# bufferedBackplane.net
KiCad netlist of a schematic drawn in EAGLE
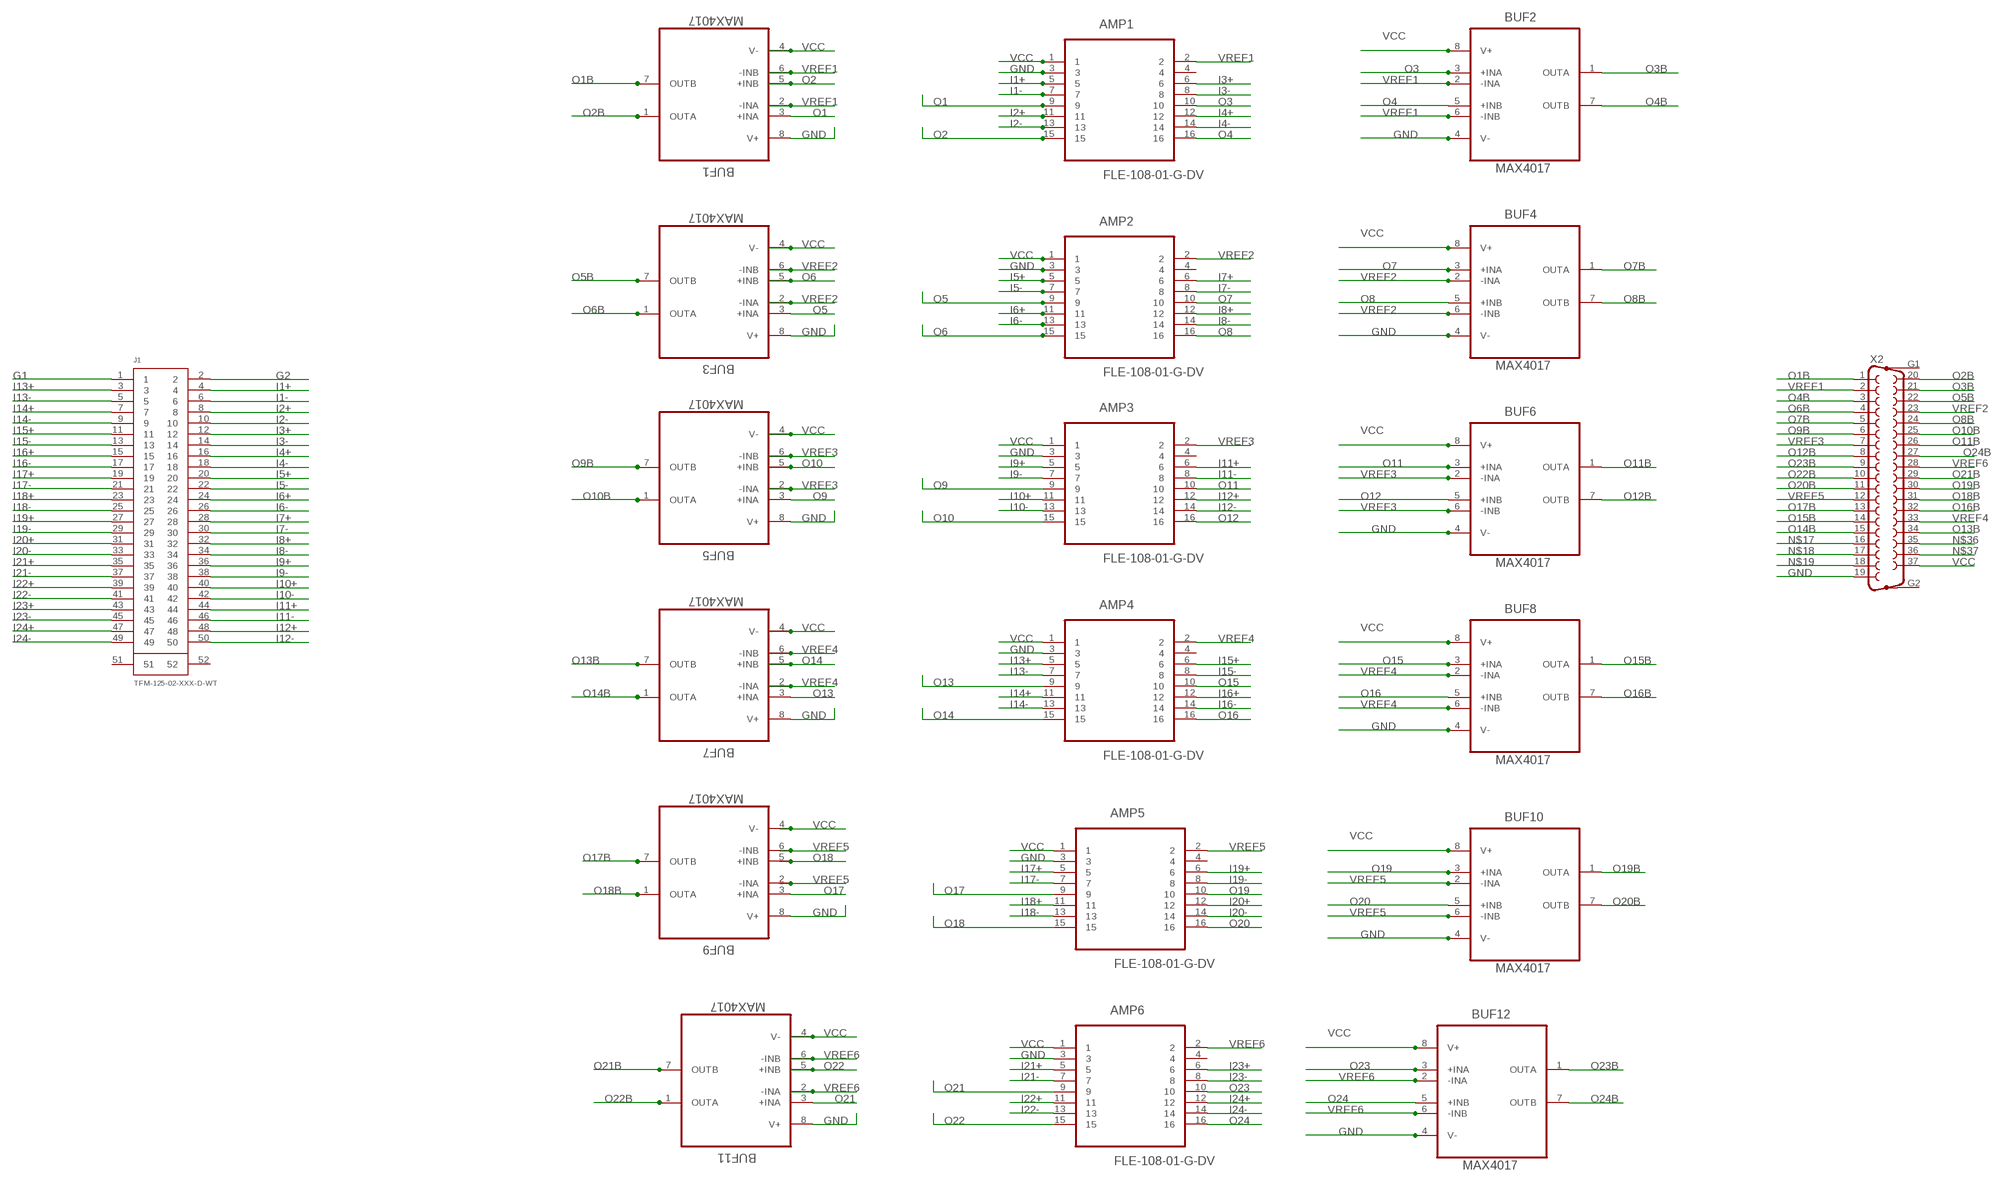
[diagram p0: schematic, sheet 1]

(export (version "E")
  (design (tool "Eeschema 10.0.6"))
  (components
    (comp (ref "AMP1")
      (value "FLE-108-01-G-DV")
      (footprint "eagle-import:SAMTEC_FLE-108-01-G-DV")
      (libsource (lib "eagle-import") (part "FLE-108-01-G-DV"))
    )
    (comp (ref "AMP2")
      (value "FLE-108-01-G-DV")
      (footprint "eagle-import:SAMTEC_FLE-108-01-G-DV")
      (libsource (lib "eagle-import") (part "FLE-108-01-G-DV"))
    )
    (comp (ref "AMP3")
      (value "FLE-108-01-G-DV")
      (footprint "eagle-import:SAMTEC_FLE-108-01-G-DV")
      (libsource (lib "eagle-import") (part "FLE-108-01-G-DV"))
    )
    (comp (ref "AMP4")
      (value "FLE-108-01-G-DV")
      (footprint "eagle-import:SAMTEC_FLE-108-01-G-DV")
      (libsource (lib "eagle-import") (part "FLE-108-01-G-DV"))
    )
    (comp (ref "AMP5")
      (value "FLE-108-01-G-DV")
      (footprint "eagle-import:SAMTEC_FLE-108-01-G-DV")
      (libsource (lib "eagle-import") (part "FLE-108-01-G-DV"))
    )
    (comp (ref "AMP6")
      (value "FLE-108-01-G-DV")
      (footprint "eagle-import:SAMTEC_FLE-108-01-G-DV")
      (libsource (lib "eagle-import") (part "FLE-108-01-G-DV"))
    )
    (comp (ref "BUF1")
      (value "MAX4017")
      (footprint "eagle-import:MAX4017")
      (libsource (lib "eagle-import") (part "MAX4017"))
    )
    (comp (ref "BUF2")
      (value "MAX4017")
      (footprint "eagle-import:MAX4017")
      (libsource (lib "eagle-import") (part "MAX4017"))
    )
    (comp (ref "BUF3")
      (value "MAX4017")
      (footprint "eagle-import:MAX4017")
      (libsource (lib "eagle-import") (part "MAX4017"))
    )
    (comp (ref "BUF4")
      (value "MAX4017")
      (footprint "eagle-import:MAX4017")
      (libsource (lib "eagle-import") (part "MAX4017"))
    )
    (comp (ref "BUF5")
      (value "MAX4017")
      (footprint "eagle-import:MAX4017")
      (libsource (lib "eagle-import") (part "MAX4017"))
    )
    (comp (ref "BUF6")
      (value "MAX4017")
      (footprint "eagle-import:MAX4017")
      (libsource (lib "eagle-import") (part "MAX4017"))
    )
    (comp (ref "BUF7")
      (value "MAX4017")
      (footprint "eagle-import:MAX4017")
      (libsource (lib "eagle-import") (part "MAX4017"))
    )
    (comp (ref "BUF8")
      (value "MAX4017")
      (footprint "eagle-import:MAX4017")
      (libsource (lib "eagle-import") (part "MAX4017"))
    )
    (comp (ref "BUF9")
      (value "MAX4017")
      (footprint "eagle-import:MAX4017")
      (libsource (lib "eagle-import") (part "MAX4017"))
    )
    (comp (ref "BUF10")
      (value "MAX4017")
      (footprint "eagle-import:MAX4017")
      (libsource (lib "eagle-import") (part "MAX4017"))
    )
    (comp (ref "BUF11")
      (value "MAX4017")
      (footprint "eagle-import:MAX4017")
      (libsource (lib "eagle-import") (part "MAX4017"))
    )
    (comp (ref "BUF12")
      (value "MAX4017")
      (footprint "eagle-import:MAX4017")
      (libsource (lib "eagle-import") (part "MAX4017"))
    )
    (comp (ref "J1")
      (value "TFM-125-02-XXX-D-WT")
      (footprint "eagle-import:TFM-125-02-XXX-D-WT")
      (libsource (lib "eagle-import") (part "TFM-125-02-XXX-D-WT"))
    )
    (comp (ref "X2")
      (value "F37HP")
      (footprint "eagle-import:F37HP")
      (libsource (lib "eagle-import") (part "F37HP"))
    )
  )
  (nets
    (net (code "1") (name "/G1") (class "Default")
      (node (ref "J1") (pin "1") (pinfunction "1_1") (pintype "bidirectional"))
    )
    (net (code "2") (name "/G2") (class "Default")
      (node (ref "J1") (pin "2") (pinfunction "2_2") (pintype "bidirectional"))
    )
    (net (code "3") (name "/GND") (class "Default")
      (node (ref "AMP1") (pin "3") (pinfunction "3_3") (pintype "passive"))
      (node (ref "AMP2") (pin "3") (pinfunction "3_3") (pintype "passive"))
      (node (ref "AMP3") (pin "3") (pinfunction "3_3") (pintype "passive"))
      (node (ref "AMP4") (pin "3") (pinfunction "3_3") (pintype "passive"))
      (node (ref "AMP5") (pin "3") (pinfunction "3_3") (pintype "passive"))
      (node (ref "AMP6") (pin "3") (pinfunction "3_3") (pintype "passive"))
      (node (ref "BUF1") (pin "8") (pinfunction "V+_8") (pintype "power_in"))
      (node (ref "BUF10") (pin "4") (pinfunction "V-_4") (pintype "power_in"))
      (node (ref "BUF11") (pin "8") (pinfunction "V+_8") (pintype "power_in"))
      (node (ref "BUF12") (pin "4") (pinfunction "V-_4") (pintype "power_in"))
      (node (ref "BUF2") (pin "4") (pinfunction "V-_4") (pintype "power_in"))
      (node (ref "BUF3") (pin "8") (pinfunction "V+_8") (pintype "power_in"))
      (node (ref "BUF4") (pin "4") (pinfunction "V-_4") (pintype "power_in"))
      (node (ref "BUF5") (pin "8") (pinfunction "V+_8") (pintype "power_in"))
      (node (ref "BUF6") (pin "4") (pinfunction "V-_4") (pintype "power_in"))
      (node (ref "BUF7") (pin "8") (pinfunction "V+_8") (pintype "power_in"))
      (node (ref "BUF8") (pin "4") (pinfunction "V-_4") (pintype "power_in"))
      (node (ref "BUF9") (pin "8") (pinfunction "V+_8") (pintype "power_in"))
      (node (ref "X2") (pin "19") (pinfunction "19_19") (pintype "passive"))
    )
    (net (code "4") (name "/I1+") (class "Default")
      (node (ref "AMP1") (pin "5") (pinfunction "5_5") (pintype "passive"))
      (node (ref "J1") (pin "4") (pinfunction "4_4") (pintype "bidirectional"))
    )
    (net (code "5") (name "/I1-") (class "Default")
      (node (ref "AMP1") (pin "7") (pinfunction "7_7") (pintype "passive"))
      (node (ref "J1") (pin "6") (pinfunction "6_6") (pintype "bidirectional"))
    )
    (net (code "6") (name "/I2+") (class "Default")
      (node (ref "AMP1") (pin "11") (pinfunction "11_11") (pintype "passive"))
      (node (ref "J1") (pin "8") (pinfunction "8_8") (pintype "bidirectional"))
    )
    (net (code "7") (name "/I2-") (class "Default")
      (node (ref "AMP1") (pin "13") (pinfunction "13_13") (pintype "passive"))
      (node (ref "J1") (pin "10") (pinfunction "10_10") (pintype "bidirectional"))
    )
    (net (code "8") (name "/I3+") (class "Default")
      (node (ref "AMP1") (pin "6") (pinfunction "6_6") (pintype "passive"))
      (node (ref "J1") (pin "12") (pinfunction "12_12") (pintype "bidirectional"))
    )
    (net (code "9") (name "/I3-") (class "Default")
      (node (ref "AMP1") (pin "8") (pinfunction "8_8") (pintype "passive"))
      (node (ref "J1") (pin "14") (pinfunction "14_14") (pintype "bidirectional"))
    )
    (net (code "10") (name "/I4+") (class "Default")
      (node (ref "AMP1") (pin "12") (pinfunction "12_12") (pintype "passive"))
      (node (ref "J1") (pin "16") (pinfunction "16_16") (pintype "bidirectional"))
    )
    (net (code "11") (name "/I4-") (class "Default")
      (node (ref "AMP1") (pin "14") (pinfunction "14_14") (pintype "passive"))
      (node (ref "J1") (pin "18") (pinfunction "18_18") (pintype "bidirectional"))
    )
    (net (code "12") (name "/I5+") (class "Default")
      (node (ref "AMP2") (pin "5") (pinfunction "5_5") (pintype "passive"))
      (node (ref "J1") (pin "20") (pinfunction "20_20") (pintype "bidirectional"))
    )
    (net (code "13") (name "/I5-") (class "Default")
      (node (ref "AMP2") (pin "7") (pinfunction "7_7") (pintype "passive"))
      (node (ref "J1") (pin "22") (pinfunction "22_22") (pintype "bidirectional"))
    )
    (net (code "14") (name "/I6+") (class "Default")
      (node (ref "AMP2") (pin "11") (pinfunction "11_11") (pintype "passive"))
      (node (ref "J1") (pin "24") (pinfunction "24_24") (pintype "bidirectional"))
    )
    (net (code "15") (name "/I6-") (class "Default")
      (node (ref "AMP2") (pin "13") (pinfunction "13_13") (pintype "passive"))
      (node (ref "J1") (pin "26") (pinfunction "26_26") (pintype "bidirectional"))
    )
    (net (code "16") (name "/I7+") (class "Default")
      (node (ref "AMP2") (pin "6") (pinfunction "6_6") (pintype "passive"))
      (node (ref "J1") (pin "28") (pinfunction "28_28") (pintype "bidirectional"))
    )
    (net (code "17") (name "/I7-") (class "Default")
      (node (ref "AMP2") (pin "8") (pinfunction "8_8") (pintype "passive"))
      (node (ref "J1") (pin "30") (pinfunction "30_30") (pintype "bidirectional"))
    )
    (net (code "18") (name "/I8+") (class "Default")
      (node (ref "AMP2") (pin "12") (pinfunction "12_12") (pintype "passive"))
      (node (ref "J1") (pin "32") (pinfunction "32_32") (pintype "bidirectional"))
    )
    (net (code "19") (name "/I8-") (class "Default")
      (node (ref "AMP2") (pin "14") (pinfunction "14_14") (pintype "passive"))
      (node (ref "J1") (pin "34") (pinfunction "34_34") (pintype "bidirectional"))
    )
    (net (code "20") (name "/I9+") (class "Default")
      (node (ref "AMP3") (pin "5") (pinfunction "5_5") (pintype "passive"))
      (node (ref "J1") (pin "36") (pinfunction "36_36") (pintype "bidirectional"))
    )
    (net (code "21") (name "/I9-") (class "Default")
      (node (ref "AMP3") (pin "7") (pinfunction "7_7") (pintype "passive"))
      (node (ref "J1") (pin "38") (pinfunction "38_38") (pintype "bidirectional"))
    )
    (net (code "22") (name "/I10+") (class "Default")
      (node (ref "AMP3") (pin "11") (pinfunction "11_11") (pintype "passive"))
      (node (ref "J1") (pin "40") (pinfunction "40_40") (pintype "bidirectional"))
    )
    (net (code "23") (name "/I10-") (class "Default")
      (node (ref "AMP3") (pin "13") (pinfunction "13_13") (pintype "passive"))
      (node (ref "J1") (pin "42") (pinfunction "42_42") (pintype "bidirectional"))
    )
    (net (code "24") (name "/I11+") (class "Default")
      (node (ref "AMP3") (pin "6") (pinfunction "6_6") (pintype "passive"))
      (node (ref "J1") (pin "44") (pinfunction "44_44") (pintype "bidirectional"))
    )
    (net (code "25") (name "/I11-") (class "Default")
      (node (ref "AMP3") (pin "8") (pinfunction "8_8") (pintype "passive"))
      (node (ref "J1") (pin "46") (pinfunction "46_46") (pintype "bidirectional"))
    )
    (net (code "26") (name "/I12+") (class "Default")
      (node (ref "AMP3") (pin "12") (pinfunction "12_12") (pintype "passive"))
      (node (ref "J1") (pin "48") (pinfunction "48_48") (pintype "bidirectional"))
    )
    (net (code "27") (name "/I12-") (class "Default")
      (node (ref "AMP3") (pin "14") (pinfunction "14_14") (pintype "passive"))
      (node (ref "J1") (pin "50") (pinfunction "50_50") (pintype "bidirectional"))
    )
    (net (code "28") (name "/I13+") (class "Default")
      (node (ref "AMP4") (pin "5") (pinfunction "5_5") (pintype "passive"))
      (node (ref "J1") (pin "3") (pinfunction "3_3") (pintype "bidirectional"))
    )
    (net (code "29") (name "/I13-") (class "Default")
      (node (ref "AMP4") (pin "7") (pinfunction "7_7") (pintype "passive"))
      (node (ref "J1") (pin "5") (pinfunction "5_5") (pintype "bidirectional"))
    )
    (net (code "30") (name "/I14+") (class "Default")
      (node (ref "AMP4") (pin "11") (pinfunction "11_11") (pintype "passive"))
      (node (ref "J1") (pin "7") (pinfunction "7_7") (pintype "bidirectional"))
    )
    (net (code "31") (name "/I14-") (class "Default")
      (node (ref "AMP4") (pin "13") (pinfunction "13_13") (pintype "passive"))
      (node (ref "J1") (pin "9") (pinfunction "9_9") (pintype "bidirectional"))
    )
    (net (code "32") (name "/I15+") (class "Default")
      (node (ref "AMP4") (pin "6") (pinfunction "6_6") (pintype "passive"))
      (node (ref "J1") (pin "11") (pinfunction "11_11") (pintype "bidirectional"))
    )
    (net (code "33") (name "/I15-") (class "Default")
      (node (ref "AMP4") (pin "8") (pinfunction "8_8") (pintype "passive"))
      (node (ref "J1") (pin "13") (pinfunction "13_13") (pintype "bidirectional"))
    )
    (net (code "34") (name "/I16+") (class "Default")
      (node (ref "AMP4") (pin "12") (pinfunction "12_12") (pintype "passive"))
      (node (ref "J1") (pin "15") (pinfunction "15_15") (pintype "bidirectional"))
    )
    (net (code "35") (name "/I16-") (class "Default")
      (node (ref "AMP4") (pin "14") (pinfunction "14_14") (pintype "passive"))
      (node (ref "J1") (pin "17") (pinfunction "17_17") (pintype "bidirectional"))
    )
    (net (code "36") (name "/I17+") (class "Default")
      (node (ref "AMP5") (pin "5") (pinfunction "5_5") (pintype "passive"))
      (node (ref "J1") (pin "19") (pinfunction "19_19") (pintype "bidirectional"))
    )
    (net (code "37") (name "/I17-") (class "Default")
      (node (ref "AMP5") (pin "7") (pinfunction "7_7") (pintype "passive"))
      (node (ref "J1") (pin "21") (pinfunction "21_21") (pintype "bidirectional"))
    )
    (net (code "38") (name "/I18+") (class "Default")
      (node (ref "AMP5") (pin "11") (pinfunction "11_11") (pintype "passive"))
      (node (ref "J1") (pin "23") (pinfunction "23_23") (pintype "bidirectional"))
    )
    (net (code "39") (name "/I18-") (class "Default")
      (node (ref "AMP5") (pin "13") (pinfunction "13_13") (pintype "passive"))
      (node (ref "J1") (pin "25") (pinfunction "25_25") (pintype "bidirectional"))
    )
    (net (code "40") (name "/I19+") (class "Default")
      (node (ref "AMP5") (pin "6") (pinfunction "6_6") (pintype "passive"))
      (node (ref "J1") (pin "27") (pinfunction "27_27") (pintype "bidirectional"))
    )
    (net (code "41") (name "/I19-") (class "Default")
      (node (ref "AMP5") (pin "8") (pinfunction "8_8") (pintype "passive"))
      (node (ref "J1") (pin "29") (pinfunction "29_29") (pintype "bidirectional"))
    )
    (net (code "42") (name "/I20+") (class "Default")
      (node (ref "AMP5") (pin "12") (pinfunction "12_12") (pintype "passive"))
      (node (ref "J1") (pin "31") (pinfunction "31_31") (pintype "bidirectional"))
    )
    (net (code "43") (name "/I20-") (class "Default")
      (node (ref "AMP5") (pin "14") (pinfunction "14_14") (pintype "passive"))
      (node (ref "J1") (pin "33") (pinfunction "33_33") (pintype "bidirectional"))
    )
    (net (code "44") (name "/I21+") (class "Default")
      (node (ref "AMP6") (pin "5") (pinfunction "5_5") (pintype "passive"))
      (node (ref "J1") (pin "35") (pinfunction "35_35") (pintype "bidirectional"))
    )
    (net (code "45") (name "/I21-") (class "Default")
      (node (ref "AMP6") (pin "7") (pinfunction "7_7") (pintype "passive"))
      (node (ref "J1") (pin "37") (pinfunction "37_37") (pintype "bidirectional"))
    )
    (net (code "46") (name "/I22+") (class "Default")
      (node (ref "AMP6") (pin "11") (pinfunction "11_11") (pintype "passive"))
      (node (ref "J1") (pin "39") (pinfunction "39_39") (pintype "bidirectional"))
    )
    (net (code "47") (name "/I22-") (class "Default")
      (node (ref "AMP6") (pin "13") (pinfunction "13_13") (pintype "passive"))
      (node (ref "J1") (pin "41") (pinfunction "41_41") (pintype "bidirectional"))
    )
    (net (code "48") (name "/I23+") (class "Default")
      (node (ref "AMP6") (pin "6") (pinfunction "6_6") (pintype "passive"))
      (node (ref "J1") (pin "43") (pinfunction "43_43") (pintype "bidirectional"))
    )
    (net (code "49") (name "/I23-") (class "Default")
      (node (ref "AMP6") (pin "8") (pinfunction "8_8") (pintype "passive"))
      (node (ref "J1") (pin "45") (pinfunction "45_45") (pintype "bidirectional"))
    )
    (net (code "50") (name "/I24+") (class "Default")
      (node (ref "AMP6") (pin "12") (pinfunction "12_12") (pintype "passive"))
      (node (ref "J1") (pin "47") (pinfunction "47_47") (pintype "bidirectional"))
    )
    (net (code "51") (name "/I24-") (class "Default")
      (node (ref "AMP6") (pin "14") (pinfunction "14_14") (pintype "passive"))
      (node (ref "J1") (pin "49") (pinfunction "49_49") (pintype "bidirectional"))
    )
    (net (code "52") (name "/N$17") (class "Default")
      (node (ref "X2") (pin "16") (pinfunction "16_16") (pintype "passive"))
    )
    (net (code "53") (name "/N$18") (class "Default")
      (node (ref "X2") (pin "17") (pinfunction "17_17") (pintype "passive"))
    )
    (net (code "54") (name "/N$19") (class "Default")
      (node (ref "X2") (pin "18") (pinfunction "18_18") (pintype "passive"))
    )
    (net (code "55") (name "/N$36") (class "Default")
      (node (ref "X2") (pin "35") (pinfunction "35_35") (pintype "passive"))
    )
    (net (code "56") (name "/N$37") (class "Default")
      (node (ref "X2") (pin "36") (pinfunction "36_36") (pintype "passive"))
    )
    (net (code "57") (name "/O1") (class "Default")
      (node (ref "AMP1") (pin "9") (pinfunction "9_9") (pintype "passive"))
      (node (ref "BUF1") (pin "3") (pinfunction "+INA_3") (pintype "input"))
    )
    (net (code "58") (name "/O1B") (class "Default")
      (node (ref "BUF1") (pin "7") (pinfunction "OUTB_7") (pintype "output"))
      (node (ref "X2") (pin "1") (pinfunction "1_1") (pintype "passive"))
    )
    (net (code "59") (name "/O2") (class "Default")
      (node (ref "AMP1") (pin "15") (pinfunction "15_15") (pintype "passive"))
      (node (ref "BUF1") (pin "5") (pinfunction "+INB_5") (pintype "input"))
    )
    (net (code "60") (name "/O2B") (class "Default")
      (node (ref "BUF1") (pin "1") (pinfunction "OUTA_1") (pintype "output"))
      (node (ref "X2") (pin "20") (pinfunction "20_20") (pintype "passive"))
    )
    (net (code "61") (name "/O3") (class "Default")
      (node (ref "AMP1") (pin "10") (pinfunction "10_10") (pintype "passive"))
      (node (ref "BUF2") (pin "3") (pinfunction "+INA_3") (pintype "input"))
    )
    (net (code "62") (name "/O3B") (class "Default")
      (node (ref "BUF2") (pin "1") (pinfunction "OUTA_1") (pintype "output"))
      (node (ref "X2") (pin "21") (pinfunction "21_21") (pintype "passive"))
    )
    (net (code "63") (name "/O4") (class "Default")
      (node (ref "AMP1") (pin "16") (pinfunction "16_16") (pintype "passive"))
      (node (ref "BUF2") (pin "5") (pinfunction "+INB_5") (pintype "input"))
    )
    (net (code "64") (name "/O4B") (class "Default")
      (node (ref "BUF2") (pin "7") (pinfunction "OUTB_7") (pintype "output"))
      (node (ref "X2") (pin "3") (pinfunction "3_3") (pintype "passive"))
    )
    (net (code "65") (name "/O5") (class "Default")
      (node (ref "AMP2") (pin "9") (pinfunction "9_9") (pintype "passive"))
      (node (ref "BUF3") (pin "3") (pinfunction "+INA_3") (pintype "input"))
    )
    (net (code "66") (name "/O5B") (class "Default")
      (node (ref "BUF3") (pin "7") (pinfunction "OUTB_7") (pintype "output"))
      (node (ref "X2") (pin "22") (pinfunction "22_22") (pintype "passive"))
    )
    (net (code "67") (name "/O6") (class "Default")
      (node (ref "AMP2") (pin "15") (pinfunction "15_15") (pintype "passive"))
      (node (ref "BUF3") (pin "5") (pinfunction "+INB_5") (pintype "input"))
    )
    (net (code "68") (name "/O6B") (class "Default")
      (node (ref "BUF3") (pin "1") (pinfunction "OUTA_1") (pintype "output"))
      (node (ref "X2") (pin "4") (pinfunction "4_4") (pintype "passive"))
    )
    (net (code "69") (name "/O7") (class "Default")
      (node (ref "AMP2") (pin "10") (pinfunction "10_10") (pintype "passive"))
      (node (ref "BUF4") (pin "3") (pinfunction "+INA_3") (pintype "input"))
    )
    (net (code "70") (name "/O7B") (class "Default")
      (node (ref "BUF4") (pin "1") (pinfunction "OUTA_1") (pintype "output"))
      (node (ref "X2") (pin "5") (pinfunction "5_5") (pintype "passive"))
    )
    (net (code "71") (name "/O8") (class "Default")
      (node (ref "AMP2") (pin "16") (pinfunction "16_16") (pintype "passive"))
      (node (ref "BUF4") (pin "5") (pinfunction "+INB_5") (pintype "input"))
    )
    (net (code "72") (name "/O8B") (class "Default")
      (node (ref "BUF4") (pin "7") (pinfunction "OUTB_7") (pintype "output"))
      (node (ref "X2") (pin "24") (pinfunction "24_24") (pintype "passive"))
    )
    (net (code "73") (name "/O9") (class "Default")
      (node (ref "AMP3") (pin "9") (pinfunction "9_9") (pintype "passive"))
      (node (ref "BUF5") (pin "3") (pinfunction "+INA_3") (pintype "input"))
    )
    (net (code "74") (name "/O9B") (class "Default")
      (node (ref "BUF5") (pin "7") (pinfunction "OUTB_7") (pintype "output"))
      (node (ref "X2") (pin "6") (pinfunction "6_6") (pintype "passive"))
    )
    (net (code "75") (name "/O10") (class "Default")
      (node (ref "AMP3") (pin "15") (pinfunction "15_15") (pintype "passive"))
      (node (ref "BUF5") (pin "5") (pinfunction "+INB_5") (pintype "input"))
    )
    (net (code "76") (name "/O10B") (class "Default")
      (node (ref "BUF5") (pin "1") (pinfunction "OUTA_1") (pintype "output"))
      (node (ref "X2") (pin "25") (pinfunction "25_25") (pintype "passive"))
    )
    (net (code "77") (name "/O11") (class "Default")
      (node (ref "AMP3") (pin "10") (pinfunction "10_10") (pintype "passive"))
      (node (ref "BUF6") (pin "3") (pinfunction "+INA_3") (pintype "input"))
    )
    (net (code "78") (name "/O11B") (class "Default")
      (node (ref "BUF6") (pin "1") (pinfunction "OUTA_1") (pintype "output"))
      (node (ref "X2") (pin "26") (pinfunction "26_26") (pintype "passive"))
    )
    (net (code "79") (name "/O12") (class "Default")
      (node (ref "AMP3") (pin "16") (pinfunction "16_16") (pintype "passive"))
      (node (ref "BUF6") (pin "5") (pinfunction "+INB_5") (pintype "input"))
    )
    (net (code "80") (name "/O12B") (class "Default")
      (node (ref "BUF6") (pin "7") (pinfunction "OUTB_7") (pintype "output"))
      (node (ref "X2") (pin "8") (pinfunction "8_8") (pintype "passive"))
    )
    (net (code "81") (name "/O13") (class "Default")
      (node (ref "AMP4") (pin "9") (pinfunction "9_9") (pintype "passive"))
      (node (ref "BUF7") (pin "3") (pinfunction "+INA_3") (pintype "input"))
    )
    (net (code "82") (name "/O13B") (class "Default")
      (node (ref "BUF7") (pin "7") (pinfunction "OUTB_7") (pintype "output"))
      (node (ref "X2") (pin "34") (pinfunction "34_34") (pintype "passive"))
    )
    (net (code "83") (name "/O14") (class "Default")
      (node (ref "AMP4") (pin "15") (pinfunction "15_15") (pintype "passive"))
      (node (ref "BUF7") (pin "5") (pinfunction "+INB_5") (pintype "input"))
    )
    (net (code "84") (name "/O14B") (class "Default")
      (node (ref "BUF7") (pin "1") (pinfunction "OUTA_1") (pintype "output"))
      (node (ref "X2") (pin "15") (pinfunction "15_15") (pintype "passive"))
    )
    (net (code "85") (name "/O15") (class "Default")
      (node (ref "AMP4") (pin "10") (pinfunction "10_10") (pintype "passive"))
      (node (ref "BUF8") (pin "3") (pinfunction "+INA_3") (pintype "input"))
    )
    (net (code "86") (name "/O15B") (class "Default")
      (node (ref "BUF8") (pin "1") (pinfunction "OUTA_1") (pintype "output"))
      (node (ref "X2") (pin "14") (pinfunction "14_14") (pintype "passive"))
    )
    (net (code "87") (name "/O16") (class "Default")
      (node (ref "AMP4") (pin "16") (pinfunction "16_16") (pintype "passive"))
      (node (ref "BUF8") (pin "5") (pinfunction "+INB_5") (pintype "input"))
    )
    (net (code "88") (name "/O16B") (class "Default")
      (node (ref "BUF8") (pin "7") (pinfunction "OUTB_7") (pintype "output"))
      (node (ref "X2") (pin "32") (pinfunction "32_32") (pintype "passive"))
    )
    (net (code "89") (name "/O17") (class "Default")
      (node (ref "AMP5") (pin "9") (pinfunction "9_9") (pintype "passive"))
      (node (ref "BUF9") (pin "3") (pinfunction "+INA_3") (pintype "input"))
    )
    (net (code "90") (name "/O17B") (class "Default")
      (node (ref "BUF9") (pin "7") (pinfunction "OUTB_7") (pintype "output"))
      (node (ref "X2") (pin "13") (pinfunction "13_13") (pintype "passive"))
    )
    (net (code "91") (name "/O18") (class "Default")
      (node (ref "AMP5") (pin "15") (pinfunction "15_15") (pintype "passive"))
      (node (ref "BUF9") (pin "5") (pinfunction "+INB_5") (pintype "input"))
    )
    (net (code "92") (name "/O18B") (class "Default")
      (node (ref "BUF9") (pin "1") (pinfunction "OUTA_1") (pintype "output"))
      (node (ref "X2") (pin "31") (pinfunction "31_31") (pintype "passive"))
    )
    (net (code "93") (name "/O19") (class "Default")
      (node (ref "AMP5") (pin "10") (pinfunction "10_10") (pintype "passive"))
      (node (ref "BUF10") (pin "3") (pinfunction "+INA_3") (pintype "input"))
    )
    (net (code "94") (name "/O19B") (class "Default")
      (node (ref "BUF10") (pin "1") (pinfunction "OUTA_1") (pintype "output"))
      (node (ref "X2") (pin "30") (pinfunction "30_30") (pintype "passive"))
    )
    (net (code "95") (name "/O20") (class "Default")
      (node (ref "AMP5") (pin "16") (pinfunction "16_16") (pintype "passive"))
      (node (ref "BUF10") (pin "5") (pinfunction "+INB_5") (pintype "input"))
    )
    (net (code "96") (name "/O20B") (class "Default")
      (node (ref "BUF10") (pin "7") (pinfunction "OUTB_7") (pintype "output"))
      (node (ref "X2") (pin "11") (pinfunction "11_11") (pintype "passive"))
    )
    (net (code "97") (name "/O21") (class "Default")
      (node (ref "AMP6") (pin "9") (pinfunction "9_9") (pintype "passive"))
      (node (ref "BUF11") (pin "3") (pinfunction "+INA_3") (pintype "input"))
    )
    (net (code "98") (name "/O21B") (class "Default")
      (node (ref "BUF11") (pin "7") (pinfunction "OUTB_7") (pintype "output"))
      (node (ref "X2") (pin "29") (pinfunction "29_29") (pintype "passive"))
    )
    (net (code "99") (name "/O22") (class "Default")
      (node (ref "AMP6") (pin "15") (pinfunction "15_15") (pintype "passive"))
      (node (ref "BUF11") (pin "5") (pinfunction "+INB_5") (pintype "input"))
    )
    (net (code "100") (name "/O22B") (class "Default")
      (node (ref "BUF11") (pin "1") (pinfunction "OUTA_1") (pintype "output"))
      (node (ref "X2") (pin "10") (pinfunction "10_10") (pintype "passive"))
    )
    (net (code "101") (name "/O23") (class "Default")
      (node (ref "AMP6") (pin "10") (pinfunction "10_10") (pintype "passive"))
      (node (ref "BUF12") (pin "3") (pinfunction "+INA_3") (pintype "input"))
    )
    (net (code "102") (name "/O23B") (class "Default")
      (node (ref "BUF12") (pin "1") (pinfunction "OUTA_1") (pintype "output"))
      (node (ref "X2") (pin "9") (pinfunction "9_9") (pintype "passive"))
    )
    (net (code "103") (name "/O24") (class "Default")
      (node (ref "AMP6") (pin "16") (pinfunction "16_16") (pintype "passive"))
      (node (ref "BUF12") (pin "5") (pinfunction "+INB_5") (pintype "input"))
    )
    (net (code "104") (name "/O24B") (class "Default")
      (node (ref "BUF12") (pin "7") (pinfunction "OUTB_7") (pintype "output"))
      (node (ref "X2") (pin "27") (pinfunction "27_27") (pintype "passive"))
    )
    (net (code "105") (name "/VCC") (class "Default")
      (node (ref "AMP1") (pin "1") (pinfunction "1_1") (pintype "passive"))
      (node (ref "AMP2") (pin "1") (pinfunction "1_1") (pintype "passive"))
      (node (ref "AMP3") (pin "1") (pinfunction "1_1") (pintype "passive"))
      (node (ref "AMP4") (pin "1") (pinfunction "1_1") (pintype "passive"))
      (node (ref "AMP5") (pin "1") (pinfunction "1_1") (pintype "passive"))
      (node (ref "AMP6") (pin "1") (pinfunction "1_1") (pintype "passive"))
      (node (ref "BUF1") (pin "4") (pinfunction "V-_4") (pintype "power_in"))
      (node (ref "BUF10") (pin "8") (pinfunction "V+_8") (pintype "power_in"))
      (node (ref "BUF11") (pin "4") (pinfunction "V-_4") (pintype "power_in"))
      (node (ref "BUF12") (pin "8") (pinfunction "V+_8") (pintype "power_in"))
      (node (ref "BUF2") (pin "8") (pinfunction "V+_8") (pintype "power_in"))
      (node (ref "BUF3") (pin "4") (pinfunction "V-_4") (pintype "power_in"))
      (node (ref "BUF4") (pin "8") (pinfunction "V+_8") (pintype "power_in"))
      (node (ref "BUF5") (pin "4") (pinfunction "V-_4") (pintype "power_in"))
      (node (ref "BUF6") (pin "8") (pinfunction "V+_8") (pintype "power_in"))
      (node (ref "BUF7") (pin "4") (pinfunction "V-_4") (pintype "power_in"))
      (node (ref "BUF8") (pin "8") (pinfunction "V+_8") (pintype "power_in"))
      (node (ref "BUF9") (pin "4") (pinfunction "V-_4") (pintype "power_in"))
      (node (ref "X2") (pin "37") (pinfunction "37_37") (pintype "passive"))
    )
    (net (code "106") (name "/VREF1") (class "Default")
      (node (ref "AMP1") (pin "2") (pinfunction "2_2") (pintype "passive"))
      (node (ref "BUF1") (pin "2") (pinfunction "-INA_2") (pintype "input"))
      (node (ref "BUF1") (pin "6") (pinfunction "-INB_6") (pintype "input"))
      (node (ref "BUF2") (pin "2") (pinfunction "-INA_2") (pintype "input"))
      (node (ref "BUF2") (pin "6") (pinfunction "-INB_6") (pintype "input"))
      (node (ref "X2") (pin "2") (pinfunction "2_2") (pintype "passive"))
    )
    (net (code "107") (name "/VREF2") (class "Default")
      (node (ref "AMP2") (pin "2") (pinfunction "2_2") (pintype "passive"))
      (node (ref "BUF3") (pin "2") (pinfunction "-INA_2") (pintype "input"))
      (node (ref "BUF3") (pin "6") (pinfunction "-INB_6") (pintype "input"))
      (node (ref "BUF4") (pin "2") (pinfunction "-INA_2") (pintype "input"))
      (node (ref "BUF4") (pin "6") (pinfunction "-INB_6") (pintype "input"))
      (node (ref "X2") (pin "23") (pinfunction "23_23") (pintype "passive"))
    )
    (net (code "108") (name "/VREF3") (class "Default")
      (node (ref "AMP3") (pin "2") (pinfunction "2_2") (pintype "passive"))
      (node (ref "BUF5") (pin "2") (pinfunction "-INA_2") (pintype "input"))
      (node (ref "BUF5") (pin "6") (pinfunction "-INB_6") (pintype "input"))
      (node (ref "BUF6") (pin "2") (pinfunction "-INA_2") (pintype "input"))
      (node (ref "BUF6") (pin "6") (pinfunction "-INB_6") (pintype "input"))
      (node (ref "X2") (pin "7") (pinfunction "7_7") (pintype "passive"))
    )
    (net (code "109") (name "/VREF4") (class "Default")
      (node (ref "AMP4") (pin "2") (pinfunction "2_2") (pintype "passive"))
      (node (ref "BUF7") (pin "2") (pinfunction "-INA_2") (pintype "input"))
      (node (ref "BUF7") (pin "6") (pinfunction "-INB_6") (pintype "input"))
      (node (ref "BUF8") (pin "2") (pinfunction "-INA_2") (pintype "input"))
      (node (ref "BUF8") (pin "6") (pinfunction "-INB_6") (pintype "input"))
      (node (ref "X2") (pin "33") (pinfunction "33_33") (pintype "passive"))
    )
    (net (code "110") (name "/VREF5") (class "Default")
      (node (ref "AMP5") (pin "2") (pinfunction "2_2") (pintype "passive"))
      (node (ref "BUF10") (pin "2") (pinfunction "-INA_2") (pintype "input"))
      (node (ref "BUF10") (pin "6") (pinfunction "-INB_6") (pintype "input"))
      (node (ref "BUF9") (pin "2") (pinfunction "-INA_2") (pintype "input"))
      (node (ref "BUF9") (pin "6") (pinfunction "-INB_6") (pintype "input"))
      (node (ref "X2") (pin "12") (pinfunction "12_12") (pintype "passive"))
    )
    (net (code "111") (name "/VREF6") (class "Default")
      (node (ref "AMP6") (pin "2") (pinfunction "2_2") (pintype "passive"))
      (node (ref "BUF11") (pin "2") (pinfunction "-INA_2") (pintype "input"))
      (node (ref "BUF11") (pin "6") (pinfunction "-INB_6") (pintype "input"))
      (node (ref "BUF12") (pin "2") (pinfunction "-INA_2") (pintype "input"))
      (node (ref "BUF12") (pin "6") (pinfunction "-INB_6") (pintype "input"))
      (node (ref "X2") (pin "28") (pinfunction "28_28") (pintype "passive"))
    )
    (net (code "112") (name "unconnected-(AMP1-Pad4)") (class "Default")
      (node (ref "AMP1") (pin "4") (pinfunction "4_4") (pintype "passive"))
    )
    (net (code "113") (name "unconnected-(AMP2-Pad4)") (class "Default")
      (node (ref "AMP2") (pin "4") (pinfunction "4_4") (pintype "passive"))
    )
    (net (code "114") (name "unconnected-(AMP3-Pad4)") (class "Default")
      (node (ref "AMP3") (pin "4") (pinfunction "4_4") (pintype "passive"))
    )
    (net (code "115") (name "unconnected-(AMP4-Pad4)") (class "Default")
      (node (ref "AMP4") (pin "4") (pinfunction "4_4") (pintype "passive"))
    )
    (net (code "116") (name "unconnected-(AMP5-Pad4)") (class "Default")
      (node (ref "AMP5") (pin "4") (pinfunction "4_4") (pintype "passive"))
    )
    (net (code "117") (name "unconnected-(AMP6-Pad4)") (class "Default")
      (node (ref "AMP6") (pin "4") (pinfunction "4_4") (pintype "passive"))
    )
    (net (code "118") (name "unconnected-(J1-Pad51)") (class "Default")
      (node (ref "J1") (pin "51") (pinfunction "51_51") (pintype "bidirectional"))
    )
    (net (code "119") (name "unconnected-(J1-Pad52)") (class "Default")
      (node (ref "J1") (pin "52") (pinfunction "52_52") (pintype "bidirectional"))
    )
    (net (code "120") (name "unconnected-(X2-PadG1)") (class "Default")
      (node (ref "X2") (pin "G1") (pinfunction "G1_G1") (pintype "passive"))
    )
    (net (code "121") (name "unconnected-(X2-PadG2)") (class "Default")
      (node (ref "X2") (pin "G2") (pinfunction "G2_G2") (pintype "passive"))
    )
  )
)
